# billdetect_ring2a.net
KiCad netlist of a schematic drawn in EAGLE
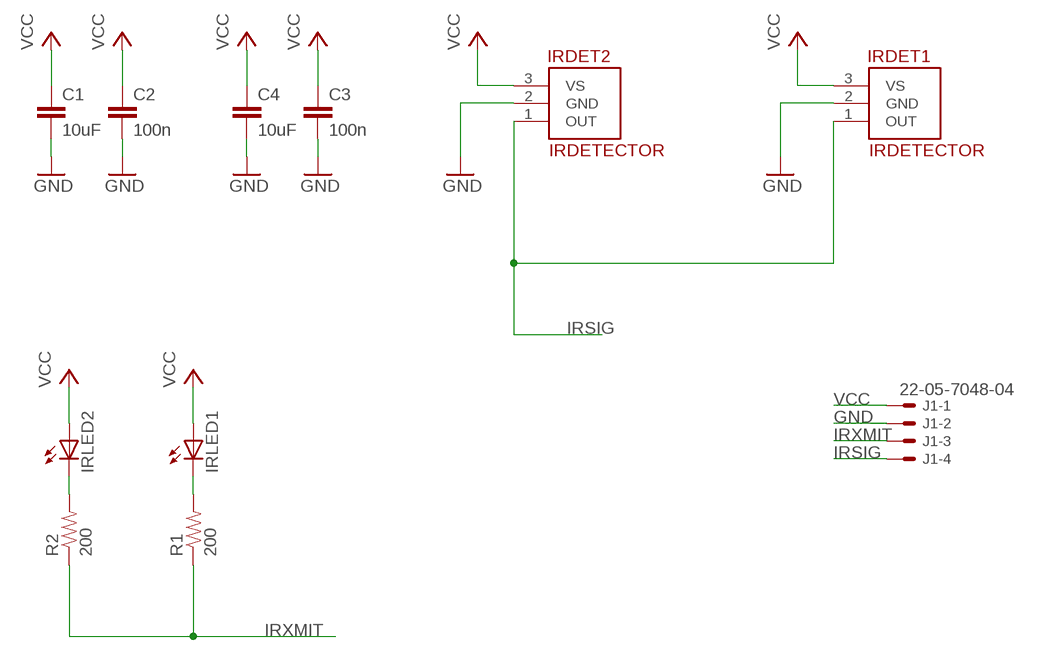
[diagram p0: schematic, sheet 1]

(export (version "E")
  (design (tool "Eeschema 10.0.6"))
  (components
    (comp (ref "C1")
      (value "10uF")
      (footprint "eagle-import:0805")
      (libsource (lib "eagle-import") (part "CAP0805"))
    )
    (comp (ref "C2")
      (value "100n")
      (footprint "eagle-import:0805")
      (libsource (lib "eagle-import") (part "CAP0805"))
    )
    (comp (ref "C3")
      (value "100n")
      (footprint "eagle-import:0805")
      (libsource (lib "eagle-import") (part "CAP0805"))
    )
    (comp (ref "C4")
      (value "10uF")
      (footprint "eagle-import:0805")
      (libsource (lib "eagle-import") (part "CAP0805"))
    )
    (comp (ref "IRDET1")
      (value "IRDETECTOR")
      (footprint "eagle-import:TSOP-3PIN-2.54MM")
      (libsource (lib "eagle-import") (part "IRDETECTOR"))
    )
    (comp (ref "IRDET2")
      (value "IRDETECTOR")
      (footprint "eagle-import:TSOP-3PIN-2.54MM")
      (libsource (lib "eagle-import") (part "IRDETECTOR"))
    )
    (comp (ref "IRLED1")
      (value "LED-5MM-90DEG")
      (footprint "eagle-import:LED-5MM-90DEG")
      (libsource (lib "eagle-import") (part "LED-5MM-90DEG"))
    )
    (comp (ref "IRLED2")
      (value "LED-5MM-90DEG")
      (footprint "eagle-import:LED-5MM-90DEG")
      (libsource (lib "eagle-import") (part "LED-5MM-90DEG"))
    )
    (comp (ref "J1")
      (value "22-05-7048-04")
      (footprint "eagle-import:7395-04")
      (libsource (lib "eagle-import") (part "22-?-0405-7048"))
    )
    (comp (ref "R1")
      (value "200")
      (footprint "eagle-import:0805")
      (libsource (lib "eagle-import") (part "RESISTOR0805-RES"))
    )
    (comp (ref "R2")
      (value "200")
      (footprint "eagle-import:0805")
      (libsource (lib "eagle-import") (part "RESISTOR0805-RES"))
    )
  )
  (nets
    (net (code "1") (name "/IRSIG") (class "Default")
      (node (ref "IRDET1") (pin "1") (pinfunction "OUT_1") (pintype "bidirectional"))
      (node (ref "IRDET2") (pin "1") (pinfunction "OUT_1") (pintype "bidirectional"))
      (node (ref "J1") (pin "4") (pinfunction "S_4") (pintype "passive"))
    )
    (net (code "2") (name "/IRXMIT") (class "Default")
      (node (ref "J1") (pin "3") (pinfunction "S_3") (pintype "passive"))
      (node (ref "R1") (pin "1") (pinfunction "1_1") (pintype "passive"))
      (node (ref "R2") (pin "1") (pinfunction "1_1") (pintype "passive"))
    )
    (net (code "3") (name "GND") (class "Default")
      (node (ref "C1") (pin "2") (pinfunction "2_2") (pintype "passive"))
      (node (ref "C2") (pin "2") (pinfunction "2_2") (pintype "passive"))
      (node (ref "C3") (pin "2") (pinfunction "2_2") (pintype "passive"))
      (node (ref "C4") (pin "2") (pinfunction "2_2") (pintype "passive"))
      (node (ref "IRDET1") (pin "2") (pinfunction "GND_2") (pintype "bidirectional"))
      (node (ref "IRDET2") (pin "2") (pinfunction "GND_2") (pintype "bidirectional"))
      (node (ref "J1") (pin "2") (pinfunction "S_2") (pintype "passive"))
    )
    (net (code "4") (name "Net-(IRLED1-C)") (class "Default")
      (node (ref "IRLED1") (pin "K") (pinfunction "C_K") (pintype "passive"))
      (node (ref "R1") (pin "2") (pinfunction "2_2") (pintype "passive"))
    )
    (net (code "5") (name "Net-(IRLED2-C)") (class "Default")
      (node (ref "IRLED2") (pin "K") (pinfunction "C_K") (pintype "passive"))
      (node (ref "R2") (pin "2") (pinfunction "2_2") (pintype "passive"))
    )
    (net (code "6") (name "VCC") (class "Default")
      (node (ref "C1") (pin "1") (pinfunction "1_1") (pintype "passive"))
      (node (ref "C2") (pin "1") (pinfunction "1_1") (pintype "passive"))
      (node (ref "C3") (pin "1") (pinfunction "1_1") (pintype "passive"))
      (node (ref "C4") (pin "1") (pinfunction "1_1") (pintype "passive"))
      (node (ref "IRDET1") (pin "3") (pinfunction "VS_3") (pintype "bidirectional"))
      (node (ref "IRDET2") (pin "3") (pinfunction "VS_3") (pintype "bidirectional"))
      (node (ref "IRLED1") (pin "A") (pinfunction "A_A") (pintype "passive"))
      (node (ref "IRLED2") (pin "A") (pinfunction "A_A") (pintype "passive"))
      (node (ref "J1") (pin "1") (pinfunction "S_1") (pintype "passive"))
    )
  )
)
